# EPS_DCDC_OR.net
KiCad netlist of a schematic drawn in Altium Designer
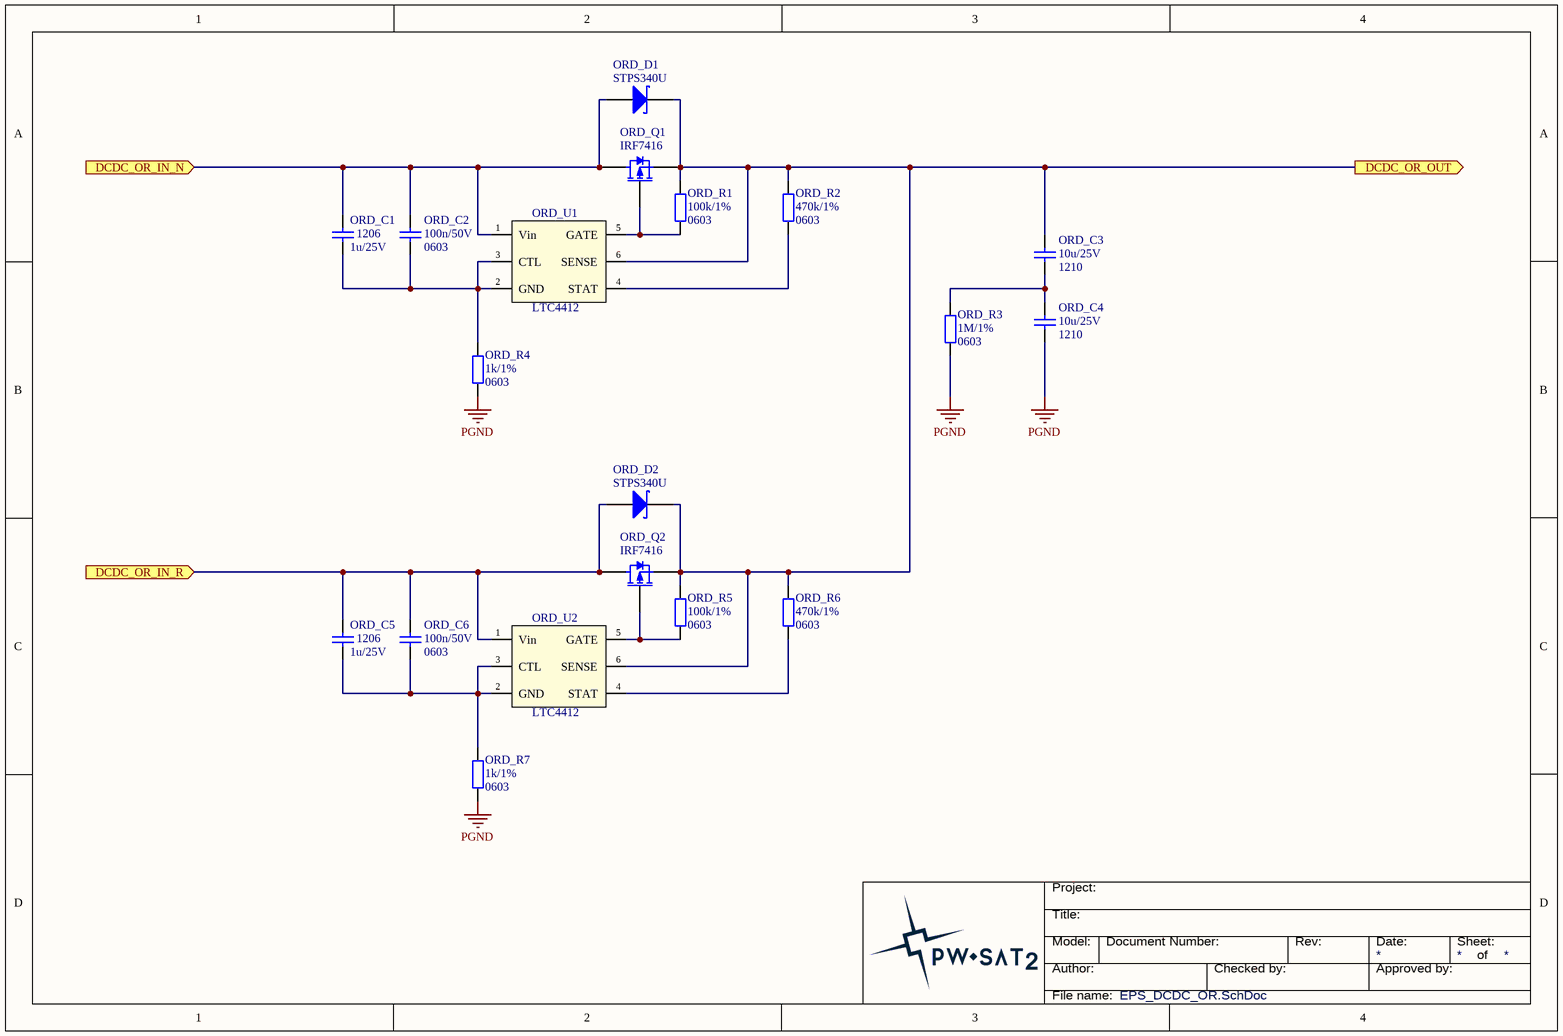
[diagram p0: EPS_DCDC_OR.SchDoc]

(export (version "E")
  (design (tool "Eeschema 10.0.6"))
  (components
    (comp (ref "ORD_C1")
      (value "1u/25V")
      (footprint "SMD_Capacitor_1206")
      (description "Ceramic Cap Kemet COTS 1u/25V X7R 1206")
      (fields
        (field (name "MANUFACTURERPARTNUMBER") "C1206T105K3RALTU")
        (field (name "MANUFACTURER") "Kemet")
        (field (name "PACKAGE") "1206")
      )
      (libsource (lib "capacitors") (part "Cer_C1206T105K3RALTU"))
    )
    (comp (ref "ORD_C2")
      (value "100n/50V")
      (footprint "SMD_Capacitor_0603")
      (description "Ceramic Cap Murata Automotive 100n/50V X7R 0603")
      (fields
        (field (name "MANUFACTURER") "Murata")
        (field (name "MANUFACTURERPARTNUMBER") "GCJ188R71H104KA12D")
        (field (name "PACKAGE") "0603")
      )
      (libsource (lib "capacitors") (part "Cer_GCJ188R71H104KA12D"))
    )
    (comp (ref "ORD_C3")
      (value "10u/25V")
      (footprint "SMD_Capacitor_1210")
      (description "Ceramic Cap Murata Automotive 10u/25V X7R 1210")
      (fields
        (field (name "MANUFACTURER") "Murata")
        (field (name "MANUFACTURERPARTNUMBER") "GCJ32ER71E106KA12L")
        (field (name "PACKAGE") "1210")
      )
      (libsource (lib "capacitors") (part "Cer_GCJ32ER71E106KA12L"))
    )
    (comp (ref "ORD_C4")
      (value "10u/25V")
      (footprint "SMD_Capacitor_1210")
      (description "Ceramic Cap Murata Automotive 10u/25V X7R 1210")
      (fields
        (field (name "MANUFACTURER") "Murata")
        (field (name "MANUFACTURERPARTNUMBER") "GCJ32ER71E106KA12L")
        (field (name "PACKAGE") "1210")
      )
      (libsource (lib "capacitors") (part "Cer_GCJ32ER71E106KA12L"))
    )
    (comp (ref "ORD_C5")
      (value "1u/25V")
      (footprint "SMD_Capacitor_1206")
      (description "Ceramic Cap Kemet COTS 1u/25V X7R 1206")
      (fields
        (field (name "MANUFACTURERPARTNUMBER") "C1206T105K3RALTU")
        (field (name "MANUFACTURER") "Kemet")
        (field (name "PACKAGE") "1206")
      )
      (libsource (lib "capacitors") (part "Cer_C1206T105K3RALTU"))
    )
    (comp (ref "ORD_C6")
      (value "100n/50V")
      (footprint "SMD_Capacitor_0603")
      (description "Ceramic Cap Murata Automotive 100n/50V X7R 0603")
      (fields
        (field (name "MANUFACTURER") "Murata")
        (field (name "MANUFACTURERPARTNUMBER") "GCJ188R71H104KA12D")
        (field (name "PACKAGE") "0603")
      )
      (libsource (lib "capacitors") (part "Cer_GCJ188R71H104KA12D"))
    )
    (comp (ref "ORD_D1")
      (value "STPS340U")
      (footprint "DO-214AA")
      (description "3A/40V Power Schottky Rectifier.")
      (fields (field (name "MANUFACTURER") "STMicroelectronics"))
      (libsource (lib "diodes") (part "STPS340x"))
    )
    (comp (ref "ORD_D2")
      (value "STPS340U")
      (footprint "DO-214AA")
      (description "3A/40V Power Schottky Rectifier.")
      (fields (field (name "MANUFACTURER") "STMicroelectronics"))
      (libsource (lib "diodes") (part "STPS340x"))
    )
    (comp (ref "ORD_Q1")
      (value "IRF7416")
      (footprint "SOIC-8-N_SSSGDDDD")
      (description "10A/30V HEXFET Power P-MOSFET.")
      (fields (field (name "MANUFACTURER") "International Rectifier"))
      (libsource (lib "transistors") (part "IRF7416"))
    )
    (comp (ref "ORD_Q2")
      (value "IRF7416")
      (footprint "SOIC-8-N_SSSGDDDD")
      (description "10A/30V HEXFET Power P-MOSFET.")
      (fields (field (name "MANUFACTURER") "International Rectifier"))
      (libsource (lib "transistors") (part "IRF7416"))
    )
    (comp (ref "ORD_R1")
      (value "100k/1%")
      (footprint "SMD_Resistor_0603")
      (fields (field (name "PACKAGE") "0603"))
      (libsource (lib "resistors") (part "Res"))
    )
    (comp (ref "ORD_R2")
      (value "470k/1%")
      (footprint "SMD_Resistor_0603")
      (fields (field (name "PACKAGE") "0603"))
      (libsource (lib "resistors") (part "Res"))
    )
    (comp (ref "ORD_R3")
      (value "1M/1%")
      (footprint "SMD_Resistor_0603")
      (fields (field (name "PACKAGE") "0603"))
      (libsource (lib "") (part "Res_1"))
    )
    (comp (ref "ORD_R4")
      (value "1k/1%")
      (footprint "SMD_Resistor_0603")
      (fields (field (name "PACKAGE") "0603"))
      (libsource (lib "resistors") (part "Res"))
    )
    (comp (ref "ORD_R5")
      (value "100k/1%")
      (footprint "SMD_Resistor_0603")
      (fields (field (name "PACKAGE") "0603"))
      (libsource (lib "resistors") (part "Res"))
    )
    (comp (ref "ORD_R6")
      (value "470k/1%")
      (footprint "SMD_Resistor_0603")
      (fields (field (name "PACKAGE") "0603"))
      (libsource (lib "resistors") (part "Res"))
    )
    (comp (ref "ORD_R7")
      (value "1k/1%")
      (footprint "SMD_Resistor_0603")
      (fields (field (name "PACKAGE") "0603"))
      (libsource (lib "resistors") (part "Res"))
    )
    (comp (ref "ORD_U1")
      (value "LTC4412")
      (footprint "SOT23-6")
      (description "Ideal Diode, Low Loss PowerPath Controller.")
      (fields (field (name "MANUFACTURER") "Linear Technology"))
      (libsource (lib "microcircuits") (part "LTC4412"))
    )
    (comp (ref "ORD_U2")
      (value "LTC4412")
      (footprint "SOT23-6")
      (description "Ideal Diode, Low Loss PowerPath Controller.")
      (fields (field (name "MANUFACTURER") "Linear Technology"))
      (libsource (lib "microcircuits") (part "LTC4412"))
    )
  )
  (nets
    (net (code "1") (name "/DCDC_OR_IN_N") (class "Default")
      (node (ref "ORD_C1") (pin "1") (pinfunction "1_1") (pintype "passive"))
      (node (ref "ORD_C2") (pin "1") (pinfunction "1_1") (pintype "passive"))
      (node (ref "ORD_D1") (pin "A") (pinfunction "A_A") (pintype "passive"))
      (node (ref "ORD_Q1") (pin "D") (pinfunction "D_D") (pintype "passive"))
      (node (ref "ORD_U1") (pin "1") (pinfunction "Vin_1") (pintype "passive"))
    )
    (net (code "2") (name "/DCDC_OR_IN_R") (class "Default")
      (node (ref "ORD_C5") (pin "1") (pinfunction "1_1") (pintype "passive"))
      (node (ref "ORD_C6") (pin "1") (pinfunction "1_1") (pintype "passive"))
      (node (ref "ORD_D2") (pin "A") (pinfunction "A_A") (pintype "passive"))
      (node (ref "ORD_Q2") (pin "D") (pinfunction "D_D") (pintype "passive"))
      (node (ref "ORD_U2") (pin "1") (pinfunction "Vin_1") (pintype "passive"))
    )
    (net (code "3") (name "/DCDC_OR_OUT") (class "Default")
      (node (ref "ORD_C3") (pin "1") (pinfunction "1_1") (pintype "passive"))
      (node (ref "ORD_D1") (pin "K") (pinfunction "K_K") (pintype "passive"))
      (node (ref "ORD_D2") (pin "K") (pinfunction "K_K") (pintype "passive"))
      (node (ref "ORD_Q1") (pin "S") (pinfunction "S_S") (pintype "passive"))
      (node (ref "ORD_Q2") (pin "S") (pinfunction "S_S") (pintype "passive"))
      (node (ref "ORD_R1") (pin "2") (pinfunction "2_2") (pintype "passive"))
      (node (ref "ORD_R2") (pin "2") (pinfunction "2_2") (pintype "passive"))
      (node (ref "ORD_R5") (pin "2") (pinfunction "2_2") (pintype "passive"))
      (node (ref "ORD_R6") (pin "2") (pinfunction "2_2") (pintype "passive"))
      (node (ref "ORD_U1") (pin "6") (pinfunction "SENSE_6") (pintype "passive"))
      (node (ref "ORD_U2") (pin "6") (pinfunction "SENSE_6") (pintype "passive"))
    )
    (net (code "4") (name "Net-(ORD_C3-Pad2)") (class "Default")
      (node (ref "ORD_C3") (pin "2") (pinfunction "2_2") (pintype "passive"))
      (node (ref "ORD_C4") (pin "1") (pinfunction "1_1") (pintype "passive"))
      (node (ref "ORD_R3") (pin "1") (pinfunction "1_1") (pintype "passive"))
    )
    (net (code "5") (name "Net-(ORD_U1-CTL)") (class "Default")
      (node (ref "ORD_C1") (pin "2") (pinfunction "2_2") (pintype "passive"))
      (node (ref "ORD_C2") (pin "2") (pinfunction "2_2") (pintype "passive"))
      (node (ref "ORD_R4") (pin "2") (pinfunction "2_2") (pintype "passive"))
      (node (ref "ORD_U1") (pin "2") (pinfunction "GND_2") (pintype "passive"))
      (node (ref "ORD_U1") (pin "3") (pinfunction "CTL_3") (pintype "passive"))
    )
    (net (code "6") (name "Net-(ORD_U1-GATE)") (class "Default")
      (node (ref "ORD_Q1") (pin "G") (pinfunction "G_G") (pintype "passive"))
      (node (ref "ORD_R1") (pin "1") (pinfunction "1_1") (pintype "passive"))
      (node (ref "ORD_U1") (pin "5") (pinfunction "GATE_5") (pintype "passive"))
    )
    (net (code "7") (name "Net-(ORD_U1-STAT)") (class "Default")
      (node (ref "ORD_R2") (pin "1") (pinfunction "1_1") (pintype "passive"))
      (node (ref "ORD_U1") (pin "4") (pinfunction "STAT_4") (pintype "passive"))
    )
    (net (code "8") (name "Net-(ORD_U2-CTL)") (class "Default")
      (node (ref "ORD_C5") (pin "2") (pinfunction "2_2") (pintype "passive"))
      (node (ref "ORD_C6") (pin "2") (pinfunction "2_2") (pintype "passive"))
      (node (ref "ORD_R7") (pin "2") (pinfunction "2_2") (pintype "passive"))
      (node (ref "ORD_U2") (pin "2") (pinfunction "GND_2") (pintype "passive"))
      (node (ref "ORD_U2") (pin "3") (pinfunction "CTL_3") (pintype "passive"))
    )
    (net (code "9") (name "Net-(ORD_U2-GATE)") (class "Default")
      (node (ref "ORD_Q2") (pin "G") (pinfunction "G_G") (pintype "passive"))
      (node (ref "ORD_R5") (pin "1") (pinfunction "1_1") (pintype "passive"))
      (node (ref "ORD_U2") (pin "5") (pinfunction "GATE_5") (pintype "passive"))
    )
    (net (code "10") (name "Net-(ORD_U2-STAT)") (class "Default")
      (node (ref "ORD_R6") (pin "1") (pinfunction "1_1") (pintype "passive"))
      (node (ref "ORD_U2") (pin "4") (pinfunction "STAT_4") (pintype "passive"))
    )
    (net (code "11") (name "PGND") (class "Default")
      (node (ref "ORD_C4") (pin "2") (pinfunction "2_2") (pintype "passive"))
      (node (ref "ORD_R3") (pin "2") (pinfunction "2_2") (pintype "passive"))
      (node (ref "ORD_R4") (pin "1") (pinfunction "1_1") (pintype "passive"))
      (node (ref "ORD_R7") (pin "1") (pinfunction "1_1") (pintype "passive"))
    )
  )
)
